# Grove_-_Infrared_Emitter_v1_1.net
KiCad netlist of a schematic drawn in EAGLE
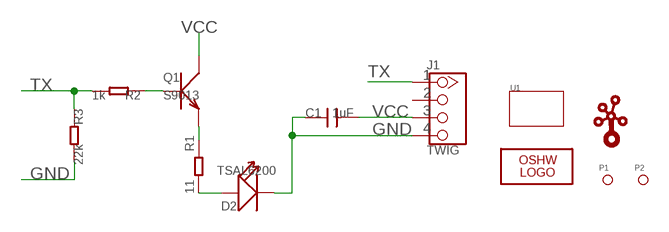
[diagram p0: schematic, sheet 1]

(export (version "E")
  (design (tool "Eeschema 10.0.6"))
  (components
    (comp (ref "C1")
      (value "1uF")
      (footprint "eagle-import:0805")
      (libsource (lib "eagle-import") (part "C-0805"))
    )
    (comp (ref "D2")
      (value "TSAL6200")
      (footprint "eagle-import:2P-LEADED-ROUND-2.54-R3.0")
      (libsource (lib "eagle-import") (part "LED-2.54"))
    )
    (comp (ref "J1")
      (value "TWIG")
      (footprint "eagle-import:4P-LEADED-2.0")
      (libsource (lib "eagle-import") (part "TWIG-2.0-LEADED-2.0"))
    )
    (comp (ref "LOGO1")
      (value "LOGO-OSHW-FILLX0150-NT")
      (footprint "eagle-import:OSHW_FILLX150_NOTEXT")
      (libsource (lib "eagle-import") (part "LOGO-OSHW-FILLX0150-NT"))
    )
    (comp (ref "P1")
      (value "PAD-MARK")
      (footprint "eagle-import:ROUND-MARK-1.0")
      (libsource (lib "eagle-import") (part "PAD-MARK"))
    )
    (comp (ref "P2")
      (value "PAD-MARK")
      (footprint "eagle-import:ROUND-MARK-1.0")
      (libsource (lib "eagle-import") (part "PAD-MARK"))
    )
    (comp (ref "Q1")
      (value "S9013")
      (footprint "eagle-import:SOT23")
      (libsource (lib "eagle-import") (part "TRANSISTOR-NPN-SOT23''"))
    )
    (comp (ref "R1")
      (value "11")
      (footprint "eagle-import:0805")
      (libsource (lib "eagle-import") (part "R-0805"))
    )
    (comp (ref "R2")
      (value "1k")
      (footprint "eagle-import:0603")
      (libsource (lib "eagle-import") (part "R-0603"))
    )
    (comp (ref "R3")
      (value "22k")
      (footprint "eagle-import:0603")
      (libsource (lib "eagle-import") (part "R-0603"))
    )
    (comp (ref "U$1")
      (value "LOGO-TWIGTWIGLOGO_SMALL")
      (footprint "eagle-import:TWIGLOGO_SMALL")
      (libsource (lib "eagle-import") (part "LOGO-TWIGTWIGLOGO_SMALL"))
    )
    (comp (ref "U1")
      (value "TWIG-1U")
      (footprint "eagle-import:1U-DIM-W_-DRILL")
      (libsource (lib "eagle-import") (part "TWIG-1U"))
    )
  )
  (nets
    (net (code "1") (name "/GND") (class "Default")
      (node (ref "C1") (pin "1") (pinfunction "1_1") (pintype "passive"))
      (node (ref "D2") (pin "-") (pinfunction "-_-") (pintype "passive"))
      (node (ref "J1") (pin "4") (pinfunction "4_4") (pintype "bidirectional"))
      (node (ref "R3") (pin "2") (pinfunction "2_2") (pintype "passive"))
    )
    (net (code "2") (name "/TX") (class "Default")
      (node (ref "J1") (pin "1") (pinfunction "1_1") (pintype "bidirectional"))
      (node (ref "R2") (pin "2") (pinfunction "2_2") (pintype "passive"))
      (node (ref "R3") (pin "1") (pinfunction "1_1") (pintype "passive"))
    )
    (net (code "3") (name "/VCC") (class "Default")
      (node (ref "C1") (pin "2") (pinfunction "2_2") (pintype "passive"))
      (node (ref "J1") (pin "3") (pinfunction "3_3") (pintype "bidirectional"))
      (node (ref "Q1") (pin "3") (pinfunction "C_3") (pintype "passive"))
    )
    (net (code "4") (name "Net-(D2-Pad+)") (class "Default")
      (node (ref "D2") (pin "+") (pinfunction "+_+") (pintype "passive"))
      (node (ref "R1") (pin "2") (pinfunction "2_2") (pintype "passive"))
    )
    (net (code "5") (name "Net-(Q1-B)") (class "Default")
      (node (ref "Q1") (pin "1") (pinfunction "B_1") (pintype "passive"))
      (node (ref "R2") (pin "1") (pinfunction "1_1") (pintype "passive"))
    )
    (net (code "6") (name "Net-(Q1-E)") (class "Default")
      (node (ref "Q1") (pin "2") (pinfunction "E_2") (pintype "passive"))
      (node (ref "R1") (pin "1") (pinfunction "1_1") (pintype "passive"))
    )
    (net (code "7") (name "unconnected-(J1-Pad2)") (class "Default")
      (node (ref "J1") (pin "2") (pinfunction "2_2") (pintype "bidirectional"))
    )
  )
)
